# USB2XXX.net
KiCad netlist of a schematic drawn in Altium Designer
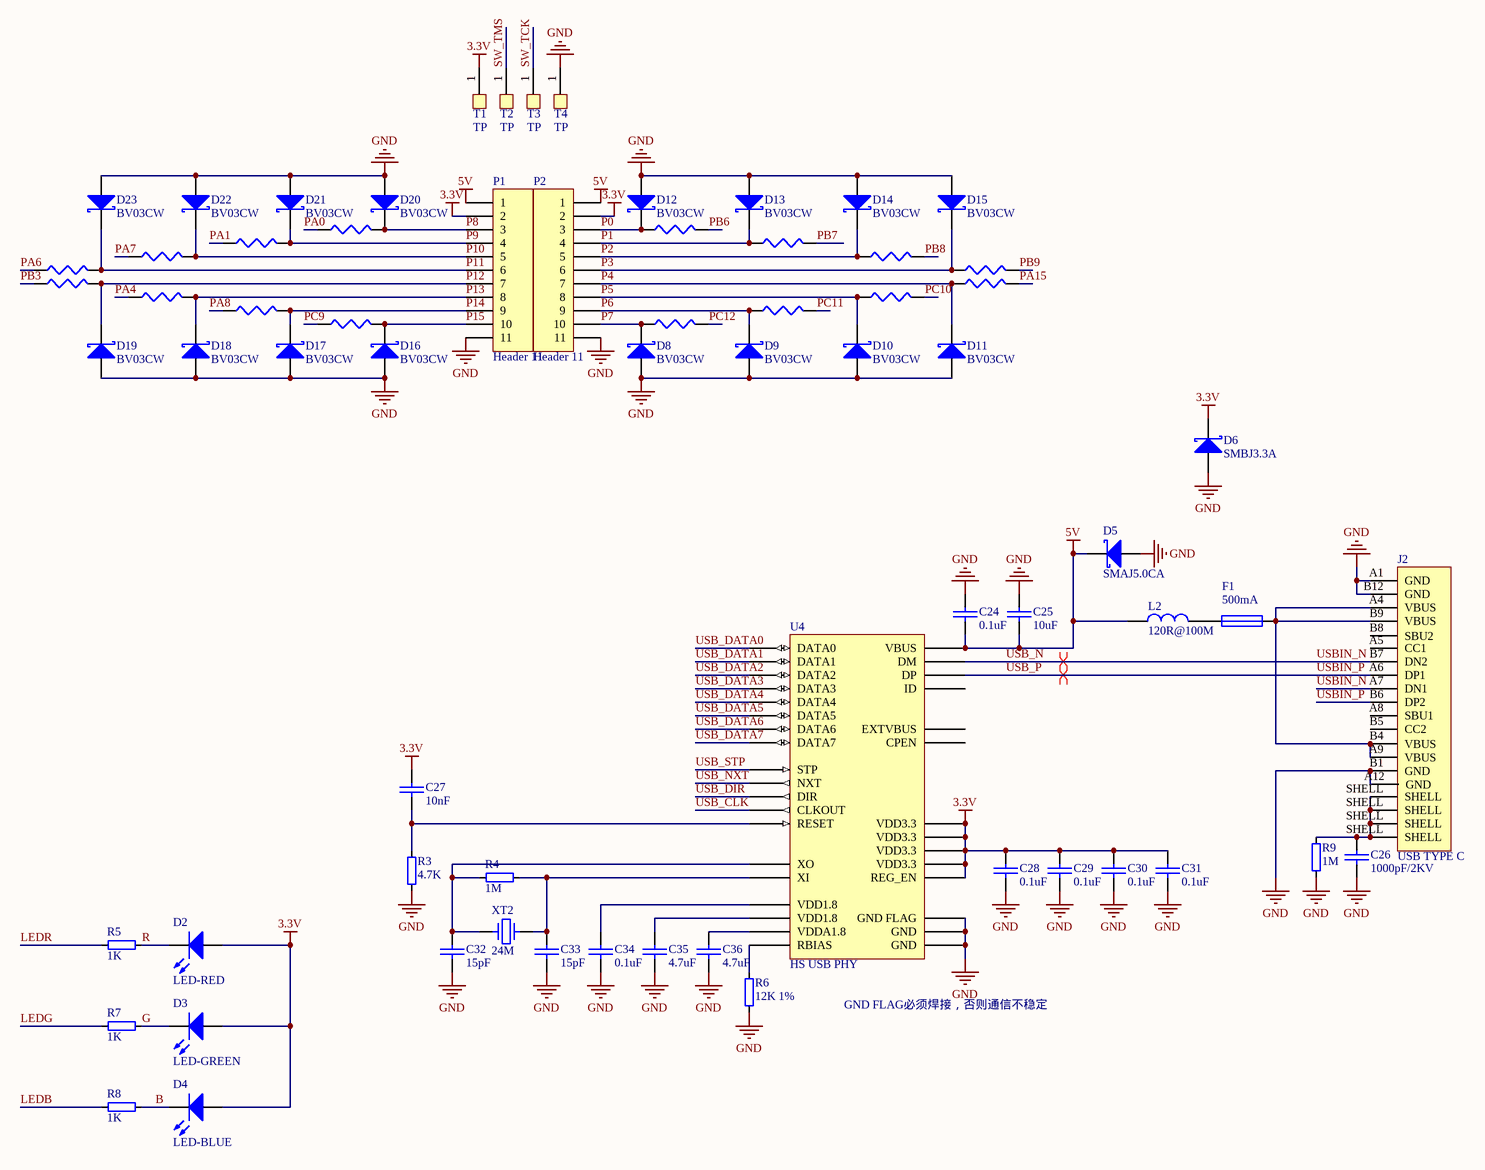
[diagram p0: USB2XXX.SchDoc]

(export (version "E")
  (design (tool "Eeschema 10.0.6"))
  (components
    (comp (ref "C24")
      (value "0.1uF")
      (footprint "C0402")
      (libsource (lib "Common Device") (part "Capacitor"))
    )
    (comp (ref "C25") (value "10uF") (footprint "C0603") (libsource (lib "Common Device") (part "Capacitor")))
    (comp (ref "C26")
      (value "1000pF/2KV")
      (footprint "Common Device:C1206")
      (libsource (lib "Common Device") (part "Capacitor"))
    )
    (comp (ref "C27") (value "10nF") (footprint "C0402") (libsource (lib "Common Device") (part "Capacitor")))
    (comp (ref "C28")
      (value "0.1uF")
      (footprint "C0402")
      (libsource (lib "Common Device") (part "Capacitor"))
    )
    (comp (ref "C29")
      (value "0.1uF")
      (footprint "C0402")
      (libsource (lib "Common Device") (part "Capacitor"))
    )
    (comp (ref "C30")
      (value "0.1uF")
      (footprint "C0402")
      (libsource (lib "Common Device") (part "Capacitor"))
    )
    (comp (ref "C31")
      (value "0.1uF")
      (footprint "C0402")
      (libsource (lib "Common Device") (part "Capacitor"))
    )
    (comp (ref "C32") (value "15pF") (footprint "C0402") (libsource (lib "Common Device") (part "Capacitor")))
    (comp (ref "C33") (value "15pF") (footprint "C0402") (libsource (lib "Common Device") (part "Capacitor")))
    (comp (ref "C34")
      (value "0.1uF")
      (footprint "C0402")
      (libsource (lib "Common Device") (part "Capacitor"))
    )
    (comp (ref "C35")
      (value "4.7uF")
      (footprint "C0402")
      (libsource (lib "Common Device") (part "Capacitor"))
    )
    (comp (ref "C36")
      (value "4.7uF")
      (footprint "C0402")
      (libsource (lib "Common Device") (part "Capacitor"))
    )
    (comp (ref "D2") (value "LED-RED") (footprint "LED0603R") (libsource (lib "Common Device") (part "LED")))
    (comp (ref "D3")
      (value "LED-GREEN")
      (footprint "LED0603G")
      (libsource (lib "Common Device") (part "LED"))
    )
    (comp (ref "D4") (value "LED-BLUE") (footprint "LED0603B") (libsource (lib "Common Device") (part "LED")))
    (comp (ref "D5")
      (value "SMAJ5.0CA")
      (footprint "DO-214AC")
      (libsource (lib "Common Device") (part "Diode Schottky"))
    )
    (comp (ref "D6")
      (value "SMBJ3.3A")
      (footprint "DO-214AA")
      (libsource (lib "Common Device") (part "Diode Schottky"))
    )
    (comp (ref "D8")
      (value "BV03CW")
      (footprint "SOD323")
      (libsource (lib "Common Device") (part "Diode Schottky"))
    )
    (comp (ref "D9")
      (value "BV03CW")
      (footprint "SOD323")
      (libsource (lib "Common Device") (part "Diode Schottky"))
    )
    (comp (ref "D10")
      (value "BV03CW")
      (footprint "SOD323")
      (libsource (lib "Common Device") (part "Diode Schottky"))
    )
    (comp (ref "D11")
      (value "BV03CW")
      (footprint "SOD323")
      (libsource (lib "Common Device") (part "Diode Schottky"))
    )
    (comp (ref "D12")
      (value "BV03CW")
      (footprint "SOD323")
      (libsource (lib "Common Device") (part "Diode Schottky"))
    )
    (comp (ref "D13")
      (value "BV03CW")
      (footprint "SOD323")
      (libsource (lib "Common Device") (part "Diode Schottky"))
    )
    (comp (ref "D14")
      (value "BV03CW")
      (footprint "SOD323")
      (libsource (lib "Common Device") (part "Diode Schottky"))
    )
    (comp (ref "D15")
      (value "BV03CW")
      (footprint "SOD323")
      (libsource (lib "Common Device") (part "Diode Schottky"))
    )
    (comp (ref "D16")
      (value "BV03CW")
      (footprint "SOD323")
      (libsource (lib "Common Device") (part "Diode Schottky"))
    )
    (comp (ref "D17")
      (value "BV03CW")
      (footprint "SOD323")
      (libsource (lib "Common Device") (part "Diode Schottky"))
    )
    (comp (ref "D18")
      (value "BV03CW")
      (footprint "SOD323")
      (libsource (lib "Common Device") (part "Diode Schottky"))
    )
    (comp (ref "D19")
      (value "BV03CW")
      (footprint "SOD323")
      (libsource (lib "Common Device") (part "Diode Schottky"))
    )
    (comp (ref "D20")
      (value "BV03CW")
      (footprint "SOD323")
      (libsource (lib "Common Device") (part "Diode Schottky"))
    )
    (comp (ref "D21")
      (value "BV03CW")
      (footprint "SOD323")
      (libsource (lib "Common Device") (part "Diode Schottky"))
    )
    (comp (ref "D22")
      (value "BV03CW")
      (footprint "SOD323")
      (libsource (lib "Common Device") (part "Diode Schottky"))
    )
    (comp (ref "D23")
      (value "BV03CW")
      (footprint "SOD323")
      (libsource (lib "Common Device") (part "Diode Schottky"))
    )
    (comp (ref "F1")
      (value "500mA")
      (footprint "R0805")
      (description "FUSE")
      (libsource (lib "RCDQLY") (part "FUSE1"))
    )
    (comp (ref "J2")
      (value "USB TYPE C")
      (footprint "USB3.1_16P")
      (libsource (lib "Common Device") (part "USB_TYPE_C"))
    )
    (comp (ref "L2")
      (value "120R@100M")
      (footprint "R0603")
      (libsource (lib "Common Device") (part "Inductor"))
    )
    (comp (ref "P1")
      (value "Header 11")
      (footprint "Common Headers:HDR1X11")
      (description "Header, 11-Pin")
      (fields (field (name "PUBLISHER") "Altium Limited"))
      (libsource (lib "Miscellaneous Connectors") (part "Header 11"))
    )
    (comp (ref "P2")
      (value "Header 11")
      (footprint "Common Headers:HDR1X11")
      (description "Header, 11-Pin")
      (fields (field (name "PUBLISHER") "Altium Limited"))
      (libsource (lib "") (part "Header 11_1"))
    )
    (comp (ref "R3")
      (value "4.7K")
      (footprint "R0402")
      (description "resistor")
      (libsource (lib "RCDQLY") (part "R-10K"))
    )
    (comp (ref "R4")
      (value "1M")
      (footprint "R0402")
      (description "resistor")
      (libsource (lib "RCDQLY") (part "R-10K"))
    )
    (comp (ref "R5")
      (value "1K")
      (footprint "R0402")
      (description "resistor")
      (libsource (lib "RCDQLY") (part "R-10K"))
    )
    (comp (ref "R6")
      (value "12K 1%")
      (footprint "R0402")
      (description "resistor")
      (libsource (lib "RCDQLY") (part "R-10K"))
    )
    (comp (ref "R7")
      (value "1K")
      (footprint "R0402")
      (description "resistor")
      (libsource (lib "RCDQLY") (part "R-10K"))
    )
    (comp (ref "R8")
      (value "1K")
      (footprint "R0402")
      (description "resistor")
      (libsource (lib "RCDQLY") (part "R-10K"))
    )
    (comp (ref "R9")
      (value "1M")
      (footprint "R0402")
      (description "resistor")
      (libsource (lib "RCDQLY") (part "R-10K"))
    )
    (comp (ref "R10") (value "0R") (footprint "R0402") (libsource (lib "Common Device") (part "Resistance")))
    (comp (ref "R11") (value "0R") (footprint "R0402") (libsource (lib "Common Device") (part "Resistance")))
    (comp (ref "R12") (value "0R") (footprint "R0402") (libsource (lib "Common Device") (part "Resistance")))
    (comp (ref "R13") (value "0R") (footprint "R0402") (libsource (lib "Common Device") (part "Resistance")))
    (comp (ref "R14") (value "0R") (footprint "R0402") (libsource (lib "Common Device") (part "Resistance")))
    (comp (ref "R15") (value "0R") (footprint "R0402") (libsource (lib "Common Device") (part "Resistance")))
    (comp (ref "R16") (value "0R") (footprint "R0402") (libsource (lib "Common Device") (part "Resistance")))
    (comp (ref "R17") (value "0R") (footprint "R0402") (libsource (lib "Common Device") (part "Resistance")))
    (comp (ref "R18") (value "0R") (footprint "R0402") (libsource (lib "Common Device") (part "Resistance")))
    (comp (ref "R19") (value "0R") (footprint "R0402") (libsource (lib "Common Device") (part "Resistance")))
    (comp (ref "R20") (value "0R") (footprint "R0402") (libsource (lib "Common Device") (part "Resistance")))
    (comp (ref "R21") (value "0R") (footprint "R0402") (libsource (lib "Common Device") (part "Resistance")))
    (comp (ref "R22") (value "0R") (footprint "R0402") (libsource (lib "Common Device") (part "Resistance")))
    (comp (ref "R23") (value "0R") (footprint "R0402") (libsource (lib "Common Device") (part "Resistance")))
    (comp (ref "R24") (value "0R") (footprint "R0402") (libsource (lib "Common Device") (part "Resistance")))
    (comp (ref "R25") (value "0R") (footprint "R0402") (libsource (lib "Common Device") (part "Resistance")))
    (comp (ref "T1") (value "TP") (footprint "TP15") (libsource (lib "Common Device") (part "TP")))
    (comp (ref "T2") (value "TP") (footprint "TP15") (libsource (lib "Common Device") (part "TP")))
    (comp (ref "T3") (value "TP") (footprint "TP15") (libsource (lib "Common Device") (part "TP")))
    (comp (ref "T4") (value "TP") (footprint "TP15") (libsource (lib "Common Device") (part "TP")))
    (comp (ref "U4")
      (value "HS USB PHY")
      (description "高速USB外置PHY")
      (libsource (lib "BusAdaptor") (part "USB3300"))
    )
    (comp (ref "XT2")
      (value "24M")
      (footprint "CRYSTAL-SMD-5032")
      (description "晶振")
      (libsource (lib "RCDQLY") (part "XT"))
    )
  )
  (nets
    (net (code "1") (name "/B") (class "Default")
      (node (ref "D4") (pin "2") (pinfunction "K_2") (pintype "passive"))
      (node (ref "R8") (pin "2") (pinfunction "2_2") (pintype "passive"))
    )
    (net (code "2") (name "/G") (class "Default")
      (node (ref "D3") (pin "2") (pinfunction "K_2") (pintype "passive"))
      (node (ref "R7") (pin "2") (pinfunction "2_2") (pintype "passive"))
    )
    (net (code "3") (name "/LEDB") (class "Default")
      (node (ref "R8") (pin "1") (pinfunction "1_1") (pintype "passive"))
    )
    (net (code "4") (name "/LEDG") (class "Default")
      (node (ref "R7") (pin "1") (pinfunction "1_1") (pintype "passive"))
    )
    (net (code "5") (name "/LEDR") (class "Default")
      (node (ref "R5") (pin "1") (pinfunction "1_1") (pintype "passive"))
    )
    (net (code "6") (name "/P0") (class "Default")
      (node (ref "D12") (pin "2") (pinfunction "K_2") (pintype "passive"))
      (node (ref "P2") (pin "3") (pinfunction "3_3") (pintype "passive"))
      (node (ref "R18") (pin "1") (pinfunction "1_1") (pintype "passive"))
    )
    (net (code "7") (name "/P1") (class "Default")
      (node (ref "D13") (pin "2") (pinfunction "K_2") (pintype "passive"))
      (node (ref "P2") (pin "4") (pinfunction "4_4") (pintype "passive"))
      (node (ref "R19") (pin "1") (pinfunction "1_1") (pintype "passive"))
    )
    (net (code "8") (name "/P2") (class "Default")
      (node (ref "D14") (pin "2") (pinfunction "K_2") (pintype "passive"))
      (node (ref "P2") (pin "5") (pinfunction "5_5") (pintype "passive"))
      (node (ref "R20") (pin "1") (pinfunction "1_1") (pintype "passive"))
    )
    (net (code "9") (name "/P3") (class "Default")
      (node (ref "D15") (pin "2") (pinfunction "K_2") (pintype "passive"))
      (node (ref "P2") (pin "6") (pinfunction "6_6") (pintype "passive"))
      (node (ref "R21") (pin "1") (pinfunction "1_1") (pintype "passive"))
    )
    (net (code "10") (name "/P4") (class "Default")
      (node (ref "D11") (pin "2") (pinfunction "K_2") (pintype "passive"))
      (node (ref "P2") (pin "7") (pinfunction "7_7") (pintype "passive"))
      (node (ref "R22") (pin "1") (pinfunction "1_1") (pintype "passive"))
    )
    (net (code "11") (name "/P5") (class "Default")
      (node (ref "D10") (pin "2") (pinfunction "K_2") (pintype "passive"))
      (node (ref "P2") (pin "8") (pinfunction "8_8") (pintype "passive"))
      (node (ref "R23") (pin "1") (pinfunction "1_1") (pintype "passive"))
    )
    (net (code "12") (name "/P6") (class "Default")
      (node (ref "D9") (pin "2") (pinfunction "K_2") (pintype "passive"))
      (node (ref "P2") (pin "9") (pinfunction "9_9") (pintype "passive"))
      (node (ref "R24") (pin "1") (pinfunction "1_1") (pintype "passive"))
    )
    (net (code "13") (name "/P7") (class "Default")
      (node (ref "D8") (pin "2") (pinfunction "K_2") (pintype "passive"))
      (node (ref "P2") (pin "10") (pinfunction "10_10") (pintype "passive"))
      (node (ref "R25") (pin "1") (pinfunction "1_1") (pintype "passive"))
    )
    (net (code "14") (name "/P8") (class "Default")
      (node (ref "D20") (pin "2") (pinfunction "K_2") (pintype "passive"))
      (node (ref "P1") (pin "3") (pinfunction "3_3") (pintype "passive"))
      (node (ref "R10") (pin "2") (pinfunction "2_2") (pintype "passive"))
    )
    (net (code "15") (name "/P9") (class "Default")
      (node (ref "D21") (pin "2") (pinfunction "K_2") (pintype "passive"))
      (node (ref "P1") (pin "4") (pinfunction "4_4") (pintype "passive"))
      (node (ref "R11") (pin "2") (pinfunction "2_2") (pintype "passive"))
    )
    (net (code "16") (name "/P10") (class "Default")
      (node (ref "D22") (pin "2") (pinfunction "K_2") (pintype "passive"))
      (node (ref "P1") (pin "5") (pinfunction "5_5") (pintype "passive"))
      (node (ref "R12") (pin "2") (pinfunction "2_2") (pintype "passive"))
    )
    (net (code "17") (name "/P11") (class "Default")
      (node (ref "D23") (pin "2") (pinfunction "K_2") (pintype "passive"))
      (node (ref "P1") (pin "6") (pinfunction "6_6") (pintype "passive"))
      (node (ref "R13") (pin "2") (pinfunction "2_2") (pintype "passive"))
    )
    (net (code "18") (name "/P12") (class "Default")
      (node (ref "D19") (pin "2") (pinfunction "K_2") (pintype "passive"))
      (node (ref "P1") (pin "7") (pinfunction "7_7") (pintype "passive"))
      (node (ref "R14") (pin "2") (pinfunction "2_2") (pintype "passive"))
    )
    (net (code "19") (name "/P13") (class "Default")
      (node (ref "D18") (pin "2") (pinfunction "K_2") (pintype "passive"))
      (node (ref "P1") (pin "8") (pinfunction "8_8") (pintype "passive"))
      (node (ref "R15") (pin "2") (pinfunction "2_2") (pintype "passive"))
    )
    (net (code "20") (name "/P14") (class "Default")
      (node (ref "D17") (pin "2") (pinfunction "K_2") (pintype "passive"))
      (node (ref "P1") (pin "9") (pinfunction "9_9") (pintype "passive"))
      (node (ref "R16") (pin "2") (pinfunction "2_2") (pintype "passive"))
    )
    (net (code "21") (name "/P15") (class "Default")
      (node (ref "D16") (pin "2") (pinfunction "K_2") (pintype "passive"))
      (node (ref "P1") (pin "10") (pinfunction "10_10") (pintype "passive"))
      (node (ref "R17") (pin "2") (pinfunction "2_2") (pintype "passive"))
    )
    (net (code "22") (name "/PA0") (class "Default")
      (node (ref "R10") (pin "1") (pinfunction "1_1") (pintype "passive"))
    )
    (net (code "23") (name "/PA1") (class "Default")
      (node (ref "R11") (pin "1") (pinfunction "1_1") (pintype "passive"))
    )
    (net (code "24") (name "/PA4") (class "Default")
      (node (ref "R15") (pin "1") (pinfunction "1_1") (pintype "passive"))
    )
    (net (code "25") (name "/PA6") (class "Default")
      (node (ref "R13") (pin "1") (pinfunction "1_1") (pintype "passive"))
    )
    (net (code "26") (name "/PA7") (class "Default")
      (node (ref "R12") (pin "1") (pinfunction "1_1") (pintype "passive"))
    )
    (net (code "27") (name "/PA8") (class "Default")
      (node (ref "R16") (pin "1") (pinfunction "1_1") (pintype "passive"))
    )
    (net (code "28") (name "/PA15") (class "Default")
      (node (ref "R22") (pin "2") (pinfunction "2_2") (pintype "passive"))
    )
    (net (code "29") (name "/PB3") (class "Default")
      (node (ref "R14") (pin "1") (pinfunction "1_1") (pintype "passive"))
    )
    (net (code "30") (name "/PB6") (class "Default")
      (node (ref "R18") (pin "2") (pinfunction "2_2") (pintype "passive"))
    )
    (net (code "31") (name "/PB7") (class "Default")
      (node (ref "R19") (pin "2") (pinfunction "2_2") (pintype "passive"))
    )
    (net (code "32") (name "/PB8") (class "Default")
      (node (ref "R20") (pin "2") (pinfunction "2_2") (pintype "passive"))
    )
    (net (code "33") (name "/PB9") (class "Default")
      (node (ref "R21") (pin "2") (pinfunction "2_2") (pintype "passive"))
    )
    (net (code "34") (name "/PC9") (class "Default")
      (node (ref "R17") (pin "1") (pinfunction "1_1") (pintype "passive"))
    )
    (net (code "35") (name "/PC10") (class "Default")
      (node (ref "R23") (pin "2") (pinfunction "2_2") (pintype "passive"))
    )
    (net (code "36") (name "/PC11") (class "Default")
      (node (ref "R24") (pin "2") (pinfunction "2_2") (pintype "passive"))
    )
    (net (code "37") (name "/PC12") (class "Default")
      (node (ref "R25") (pin "2") (pinfunction "2_2") (pintype "passive"))
    )
    (net (code "38") (name "/R") (class "Default")
      (node (ref "D2") (pin "2") (pinfunction "K_2") (pintype "passive"))
      (node (ref "R5") (pin "2") (pinfunction "2_2") (pintype "passive"))
    )
    (net (code "39") (name "/SW_TCK") (class "Default") (node (ref "T3") (pin "1") (pintype "power_in")))
    (net (code "40") (name "/SW_TMS") (class "Default") (node (ref "T2") (pin "1") (pintype "power_in")))
    (net (code "41") (name "/USBIN_N") (class "Default")
      (node (ref "J2") (pin "A7") (pinfunction "DN1_A7") (pintype "passive"))
      (node (ref "J2") (pin "B7") (pinfunction "DN2_B7") (pintype "passive"))
      (node (ref "U4") (pin "8") (pinfunction "DM_8") (pintype "passive"))
    )
    (net (code "42") (name "/USBIN_P") (class "Default")
      (node (ref "J2") (pin "A6") (pinfunction "DP1_A6") (pintype "passive"))
      (node (ref "J2") (pin "B6") (pinfunction "DP2_B6") (pintype "passive"))
      (node (ref "U4") (pin "7") (pinfunction "DP_7") (pintype "passive"))
    )
    (net (code "43") (name "/USB_CLK") (class "Default")
      (node (ref "U4") (pin "14") (pinfunction "CLKOUT_14") (pintype "output"))
    )
    (net (code "44") (name "/USB_DATA0") (class "Default")
      (node (ref "U4") (pin "24") (pinfunction "DATA0_24") (pintype "bidirectional"))
    )
    (net (code "45") (name "/USB_DATA1") (class "Default")
      (node (ref "U4") (pin "23") (pinfunction "DATA1_23") (pintype "bidirectional"))
    )
    (net (code "46") (name "/USB_DATA2") (class "Default")
      (node (ref "U4") (pin "22") (pinfunction "DATA2_22") (pintype "bidirectional"))
    )
    (net (code "47") (name "/USB_DATA3") (class "Default")
      (node (ref "U4") (pin "21") (pinfunction "DATA3_21") (pintype "bidirectional"))
    )
    (net (code "48") (name "/USB_DATA4") (class "Default")
      (node (ref "U4") (pin "20") (pinfunction "DATA4_20") (pintype "bidirectional"))
    )
    (net (code "49") (name "/USB_DATA5") (class "Default")
      (node (ref "U4") (pin "19") (pinfunction "DATA5_19") (pintype "bidirectional"))
    )
    (net (code "50") (name "/USB_DATA6") (class "Default")
      (node (ref "U4") (pin "18") (pinfunction "DATA6_18") (pintype "bidirectional"))
    )
    (net (code "51") (name "/USB_DATA7") (class "Default")
      (node (ref "U4") (pin "17") (pinfunction "DATA7_17") (pintype "bidirectional"))
    )
    (net (code "52") (name "/USB_DIR") (class "Default")
      (node (ref "U4") (pin "12") (pinfunction "DIR_12") (pintype "output"))
    )
    (net (code "53") (name "/USB_NXT") (class "Default")
      (node (ref "U4") (pin "11") (pinfunction "NXT_11") (pintype "output"))
    )
    (net (code "54") (name "/USB_STP") (class "Default")
      (node (ref "U4") (pin "13") (pinfunction "STP_13") (pintype "input"))
    )
    (net (code "55") (name "3.3V") (class "Default")
      (node (ref "C27") (pin "2") (pinfunction "2_2") (pintype "passive"))
      (node (ref "C28") (pin "2") (pinfunction "2_2") (pintype "passive"))
      (node (ref "C29") (pin "2") (pinfunction "2_2") (pintype "passive"))
      (node (ref "C30") (pin "2") (pinfunction "2_2") (pintype "passive"))
      (node (ref "C31") (pin "2") (pinfunction "2_2") (pintype "passive"))
      (node (ref "D2") (pin "1") (pinfunction "A_1") (pintype "passive"))
      (node (ref "D3") (pin "1") (pinfunction "A_1") (pintype "passive"))
      (node (ref "D4") (pin "1") (pinfunction "A_1") (pintype "passive"))
      (node (ref "D6") (pin "2") (pinfunction "K_2") (pintype "passive"))
      (node (ref "P1") (pin "2") (pinfunction "2_2") (pintype "passive"))
      (node (ref "P2") (pin "2") (pinfunction "2_2") (pintype "passive"))
      (node (ref "T1") (pin "1") (pintype "power_in"))
      (node (ref "U4") (pin "16") (pinfunction "VDD3.3_16") (pintype "power_in"))
      (node (ref "U4") (pin "25") (pinfunction "VDD3.3_25") (pintype "power_in"))
      (node (ref "U4") (pin "30") (pinfunction "VDD3.3_30") (pintype "power_in"))
      (node (ref "U4") (pin "31") (pinfunction "REG_EN_31") (pintype "passive"))
      (node (ref "U4") (pin "6") (pinfunction "VDD3.3_6") (pintype "power_in"))
    )
    (net (code "56") (name "5V") (class "Default")
      (node (ref "C24") (pin "1") (pinfunction "1_1") (pintype "passive"))
      (node (ref "C25") (pin "1") (pinfunction "1_1") (pintype "passive"))
      (node (ref "D5") (pin "2") (pinfunction "K_2") (pintype "passive"))
      (node (ref "L2") (pin "1") (pinfunction "1_1") (pintype "passive"))
      (node (ref "P1") (pin "1") (pinfunction "1_1") (pintype "passive"))
      (node (ref "P2") (pin "1") (pinfunction "1_1") (pintype "passive"))
      (node (ref "U4") (pin "4") (pinfunction "VBUS_4") (pintype "power_in"))
    )
    (net (code "57") (name "GND") (class "Default")
      (node (ref "C24") (pin "2") (pinfunction "2_2") (pintype "passive"))
      (node (ref "C25") (pin "2") (pinfunction "2_2") (pintype "passive"))
      (node (ref "C26") (pin "2") (pinfunction "2_2") (pintype "passive"))
      (node (ref "C28") (pin "1") (pinfunction "1_1") (pintype "passive"))
      (node (ref "C29") (pin "1") (pinfunction "1_1") (pintype "passive"))
      (node (ref "C30") (pin "1") (pinfunction "1_1") (pintype "passive"))
      (node (ref "C31") (pin "1") (pinfunction "1_1") (pintype "passive"))
      (node (ref "C32") (pin "1") (pinfunction "1_1") (pintype "passive"))
      (node (ref "C33") (pin "1") (pinfunction "1_1") (pintype "passive"))
      (node (ref "C34") (pin "1") (pinfunction "1_1") (pintype "passive"))
      (node (ref "C35") (pin "1") (pinfunction "1_1") (pintype "passive"))
      (node (ref "C36") (pin "1") (pinfunction "1_1") (pintype "passive"))
      (node (ref "D10") (pin "1") (pinfunction "A_1") (pintype "passive"))
      (node (ref "D11") (pin "1") (pinfunction "A_1") (pintype "passive"))
      (node (ref "D12") (pin "1") (pinfunction "A_1") (pintype "passive"))
      (node (ref "D13") (pin "1") (pinfunction "A_1") (pintype "passive"))
      (node (ref "D14") (pin "1") (pinfunction "A_1") (pintype "passive"))
      (node (ref "D15") (pin "1") (pinfunction "A_1") (pintype "passive"))
      (node (ref "D16") (pin "1") (pinfunction "A_1") (pintype "passive"))
      (node (ref "D17") (pin "1") (pinfunction "A_1") (pintype "passive"))
      (node (ref "D18") (pin "1") (pinfunction "A_1") (pintype "passive"))
      (node (ref "D19") (pin "1") (pinfunction "A_1") (pintype "passive"))
      (node (ref "D20") (pin "1") (pinfunction "A_1") (pintype "passive"))
      (node (ref "D21") (pin "1") (pinfunction "A_1") (pintype "passive"))
      (node (ref "D22") (pin "1") (pinfunction "A_1") (pintype "passive"))
      (node (ref "D23") (pin "1") (pinfunction "A_1") (pintype "passive"))
      (node (ref "D5") (pin "1") (pinfunction "A_1") (pintype "passive"))
      (node (ref "D6") (pin "1") (pinfunction "A_1") (pintype "passive"))
      (node (ref "D8") (pin "1") (pinfunction "A_1") (pintype "passive"))
      (node (ref "D9") (pin "1") (pinfunction "A_1") (pintype "passive"))
      (node (ref "J2") (pin "A1") (pinfunction "GND_A1") (pintype "passive"))
      (node (ref "J2") (pin "A12") (pinfunction "GND_A12") (pintype "passive"))
      (node (ref "J2") (pin "B1") (pinfunction "GND_B1") (pintype "passive"))
      (node (ref "J2") (pin "B12") (pinfunction "GND_B12") (pintype "passive"))
      (node (ref "P1") (pin "11") (pinfunction "11_11") (pintype "passive"))
      (node (ref "P2") (pin "11") (pinfunction "11_11") (pintype "passive"))
      (node (ref "R3") (pin "1") (pinfunction "1_1") (pintype "passive"))
      (node (ref "R6") (pin "1") (pinfunction "1_1") (pintype "passive"))
      (node (ref "R9") (pin "1") (pinfunction "1_1") (pintype "passive"))
      (node (ref "T4") (pin "1") (pintype "power_in"))
      (node (ref "U4") (pin "0") (pinfunction "GND_FLAG_0") (pintype "power_in"))
      (node (ref "U4") (pin "1") (pinfunction "GND_1") (pintype "power_in"))
      (node (ref "U4") (pin "2") (pinfunction "GND_2") (pintype "power_in"))
    )
    (net (code "58") (name "Net-(C26-Pad1)") (class "Default")
      (node (ref "C26") (pin "1") (pinfunction "1_1") (pintype "passive"))
      (node (ref "J2") (pin "SHELL") (pinfunction "SHELL_SHELL") (pintype "passive"))
      (node (ref "R9") (pin "2") (pinfunction "2_2") (pintype "passive"))
    )
    (net (code "59") (name "Net-(C34-Pad2)") (class "Default")
      (node (ref "C34") (pin "2") (pinfunction "2_2") (pintype "passive"))
      (node (ref "U4") (pin "15") (pinfunction "VDD1.8_15") (pintype "power_in"))
    )
    (net (code "60") (name "Net-(C35-Pad2)") (class "Default")
      (node (ref "C35") (pin "2") (pinfunction "2_2") (pintype "passive"))
      (node (ref "U4") (pin "26") (pinfunction "VDD1.8_26") (pintype "power_in"))
    )
    (net (code "61") (name "Net-(F1-Pad1)") (class "Default")
      (node (ref "F1") (pin "1") (pinfunction "1_1") (pintype "passive"))
      (node (ref "L2") (pin "2") (pinfunction "2_2") (pintype "passive"))
    )
    (net (code "62") (name "Net-(F1-Pad2)") (class "Default")
      (node (ref "F1") (pin "2") (pinfunction "2_2") (pintype "passive"))
      (node (ref "J2") (pin "A4") (pinfunction "VBUS_A4") (pintype "passive"))
      (node (ref "J2") (pin "A9") (pinfunction "VBUS_A9") (pintype "passive"))
      (node (ref "J2") (pin "B4") (pinfunction "VBUS_B4") (pintype "passive"))
      (node (ref "J2") (pin "B9") (pinfunction "VBUS_B9") (pintype "passive"))
    )
    (net (code "63") (name "Net-(U4-RBIAS)") (class "Default")
      (node (ref "R6") (pin "2") (pinfunction "2_2") (pintype "passive"))
      (node (ref "U4") (pin "32") (pinfunction "RBIAS_32") (pintype "passive"))
    )
    (net (code "64") (name "Net-(U4-RESET)") (class "Default")
      (node (ref "C27") (pin "1") (pinfunction "1_1") (pintype "passive"))
      (node (ref "R3") (pin "2") (pinfunction "2_2") (pintype "passive"))
      (node (ref "U4") (pin "9") (pinfunction "RESET_9") (pintype "input"))
    )
    (net (code "65") (name "Net-(U4-VDDA1.8)") (class "Default")
      (node (ref "C36") (pin "2") (pinfunction "2_2") (pintype "passive"))
      (node (ref "U4") (pin "29") (pinfunction "VDDA1.8_29") (pintype "power_in"))
    )
    (net (code "66") (name "Net-(U4-XI)") (class "Default")
      (node (ref "C33") (pin "2") (pinfunction "2_2") (pintype "passive"))
      (node (ref "R4") (pin "2") (pinfunction "2_2") (pintype "passive"))
      (node (ref "U4") (pin "28") (pinfunction "XI_28") (pintype "passive"))
      (node (ref "XT2") (pin "2") (pinfunction "2_2") (pintype "passive"))
    )
    (net (code "67") (name "Net-(U4-XO)") (class "Default")
      (node (ref "C32") (pin "2") (pinfunction "2_2") (pintype "passive"))
      (node (ref "R4") (pin "1") (pinfunction "1_1") (pintype "passive"))
      (node (ref "U4") (pin "27") (pinfunction "XO_27") (pintype "passive"))
      (node (ref "XT2") (pin "1") (pinfunction "1_1") (pintype "passive"))
    )
    (net (code "68") (name "unconnected-(J2-CC1-PadA5)") (class "Default")
      (node (ref "J2") (pin "A5") (pinfunction "CC1_A5") (pintype "passive"))
    )
    (net (code "69") (name "unconnected-(J2-CC2-PadB5)") (class "Default")
      (node (ref "J2") (pin "B5") (pinfunction "CC2_B5") (pintype "passive"))
    )
    (net (code "70") (name "unconnected-(J2-SBU1-PadA8)") (class "Default")
      (node (ref "J2") (pin "A8") (pinfunction "SBU1_A8") (pintype "passive"))
    )
    (net (code "71") (name "unconnected-(J2-SBU2-PadB8)") (class "Default")
      (node (ref "J2") (pin "B8") (pinfunction "SBU2_B8") (pintype "passive"))
    )
    (net (code "72") (name "unconnected-(U4-CPEN-Pad3)") (class "Default")
      (node (ref "U4") (pin "3") (pinfunction "CPEN_3") (pintype "power_in"))
    )
    (net (code "73") (name "unconnected-(U4-EXTVBUS-Pad10)") (class "Default")
      (node (ref "U4") (pin "10") (pinfunction "EXTVBUS_10") (pintype "passive"))
    )
    (net (code "74") (name "unconnected-(U4-ID-Pad5)") (class "Default")
      (node (ref "U4") (pin "5") (pinfunction "ID_5") (pintype "passive"))
    )
  )
)
